# MCPGrundplatte8Eingabe_8Ausgabe.net
KiCad netlist of a schematic drawn in EAGLE
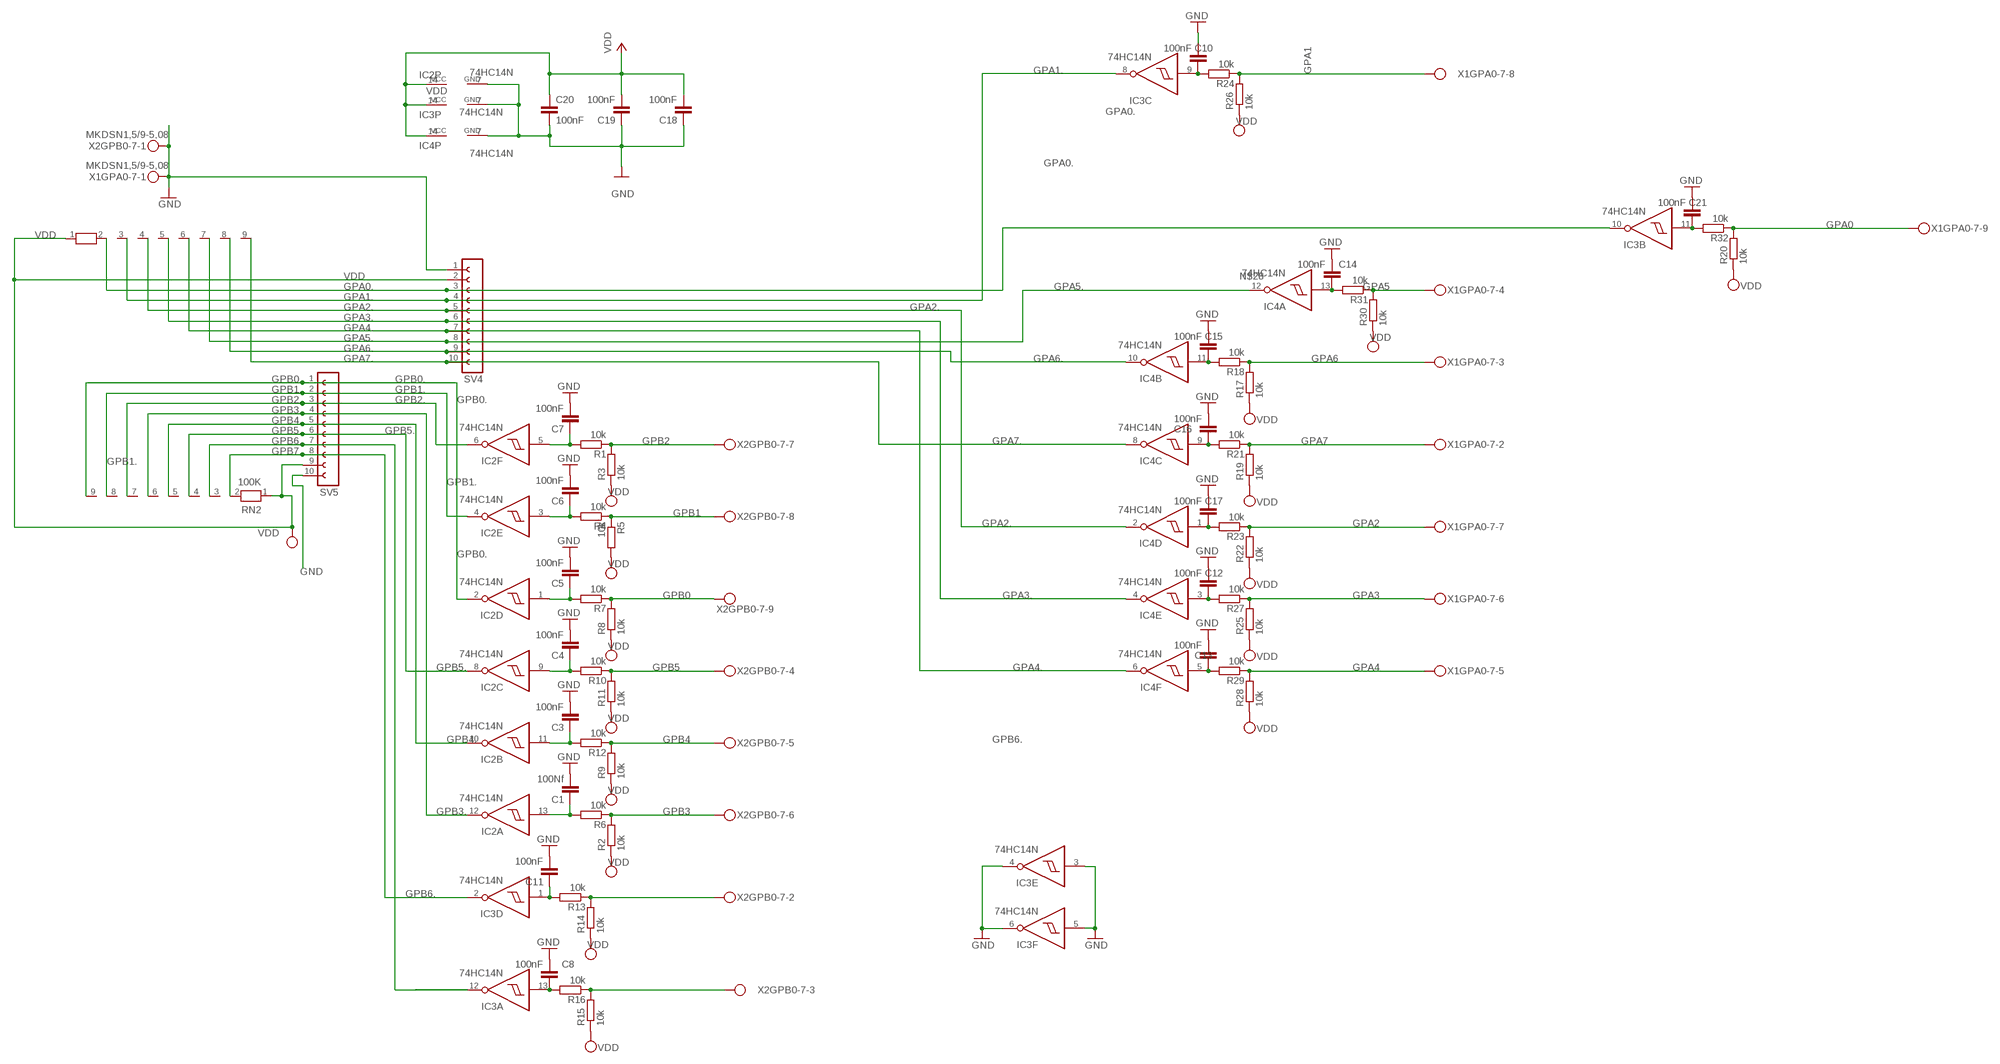
[diagram p0: schematic, sheet 1]

(export (version "E")
  (design (tool "Eeschema 10.0.6"))
  (components
    (comp (ref "C1")
      (value "100Nf")
      (footprint "eagle-import:C025-024X044")
      (libsource (lib "eagle-import") (part "C-EU025-024X044"))
    )
    (comp (ref "C3")
      (value "100nF")
      (footprint "eagle-import:C025-024X044")
      (libsource (lib "eagle-import") (part "C-EU025-024X044"))
    )
    (comp (ref "C4")
      (value "100nF")
      (footprint "eagle-import:C025-024X044")
      (libsource (lib "eagle-import") (part "C-EU025-024X044"))
    )
    (comp (ref "C5")
      (value "100nF")
      (footprint "eagle-import:C025-024X044")
      (libsource (lib "eagle-import") (part "C-EU025-024X044"))
    )
    (comp (ref "C6")
      (value "100nF")
      (footprint "eagle-import:C025-024X044")
      (libsource (lib "eagle-import") (part "C-EU025-024X044"))
    )
    (comp (ref "C7")
      (value "100nF")
      (footprint "eagle-import:C025-024X044")
      (libsource (lib "eagle-import") (part "C-EU025-024X044"))
    )
    (comp (ref "C8")
      (value "100nF")
      (footprint "eagle-import:C025-024X044")
      (libsource (lib "eagle-import") (part "C-EU025-024X044"))
    )
    (comp (ref "C10")
      (value "100nF")
      (footprint "eagle-import:C025-024X044")
      (libsource (lib "eagle-import") (part "C-EU025-024X044"))
    )
    (comp (ref "C11")
      (value "100nF")
      (footprint "eagle-import:C025-024X044")
      (libsource (lib "eagle-import") (part "C-EU025-024X044"))
    )
    (comp (ref "C12")
      (value "100nF")
      (footprint "eagle-import:C025-024X044")
      (libsource (lib "eagle-import") (part "C-EU025-024X044"))
    )
    (comp (ref "C13")
      (value "100nF")
      (footprint "eagle-import:C025-024X044")
      (libsource (lib "eagle-import") (part "C-EU025-024X044"))
    )
    (comp (ref "C14")
      (value "100nF")
      (footprint "eagle-import:C025-024X044")
      (libsource (lib "eagle-import") (part "C-EU025-024X044"))
    )
    (comp (ref "C15")
      (value "100nF")
      (footprint "eagle-import:C025-024X044")
      (libsource (lib "eagle-import") (part "C-EU025-024X044"))
    )
    (comp (ref "C16")
      (value "100nF")
      (footprint "eagle-import:C025-024X044")
      (libsource (lib "eagle-import") (part "C-EU025-024X044"))
    )
    (comp (ref "C17")
      (value "100nF")
      (footprint "eagle-import:C025-024X044")
      (libsource (lib "eagle-import") (part "C-EU025-024X044"))
    )
    (comp (ref "C18")
      (value "100nF")
      (footprint "eagle-import:C025-024X044")
      (libsource (lib "eagle-import") (part "C-EU025-024X044"))
    )
    (comp (ref "C19")
      (value "100nF")
      (footprint "eagle-import:C025-024X044")
      (libsource (lib "eagle-import") (part "C-EU025-024X044"))
    )
    (comp (ref "C20")
      (value "100nF")
      (footprint "eagle-import:C025-024X044")
      (libsource (lib "eagle-import") (part "C-EU025-024X044"))
    )
    (comp (ref "C21")
      (value "100nF")
      (footprint "eagle-import:C025-024X044")
      (libsource (lib "eagle-import") (part "C-EU025-024X044"))
    )
    (comp (ref "IC2")
      (value "74HC14N")
      (footprint "eagle-import:DIL14")
      (libsource (lib "eagle-import") (part "7414NHC"))
    )
    (comp (ref "IC3")
      (value "74HC14N")
      (footprint "eagle-import:DIL14")
      (libsource (lib "eagle-import") (part "7414NHC"))
    )
    (comp (ref "IC4")
      (value "74HC14N")
      (footprint "eagle-import:DIL14")
      (libsource (lib "eagle-import") (part "7414NHC"))
    )
    (comp (ref "R1")
      (value "10k")
      (footprint "eagle-import:0207_10")
      (libsource (lib "eagle-import") (part "R-EU_0207/10"))
    )
    (comp (ref "R2")
      (value "10k")
      (footprint "eagle-import:0207_10")
      (libsource (lib "eagle-import") (part "R-EU_0207/10"))
    )
    (comp (ref "R3")
      (value "10k")
      (footprint "eagle-import:0207_10")
      (libsource (lib "eagle-import") (part "R-EU_0207/10"))
    )
    (comp (ref "R4")
      (value "10k")
      (footprint "eagle-import:0207_10")
      (libsource (lib "eagle-import") (part "R-EU_0207/10"))
    )
    (comp (ref "R5")
      (value "10k")
      (footprint "eagle-import:0207_10")
      (libsource (lib "eagle-import") (part "R-EU_0207/10"))
    )
    (comp (ref "R6")
      (value "10k")
      (footprint "eagle-import:0207_10")
      (libsource (lib "eagle-import") (part "R-EU_0207/10"))
    )
    (comp (ref "R7")
      (value "10k")
      (footprint "eagle-import:0207_10")
      (libsource (lib "eagle-import") (part "R-EU_0207/10"))
    )
    (comp (ref "R8")
      (value "10k")
      (footprint "eagle-import:0207_10")
      (libsource (lib "eagle-import") (part "R-EU_0207/10"))
    )
    (comp (ref "R9")
      (value "10k")
      (footprint "eagle-import:0207_10")
      (libsource (lib "eagle-import") (part "R-EU_0207/10"))
    )
    (comp (ref "R10")
      (value "10k")
      (footprint "eagle-import:0207_10")
      (libsource (lib "eagle-import") (part "R-EU_0207/10"))
    )
    (comp (ref "R11")
      (value "10k")
      (footprint "eagle-import:0207_10")
      (libsource (lib "eagle-import") (part "R-EU_0207/10"))
    )
    (comp (ref "R12")
      (value "10k")
      (footprint "eagle-import:0207_10")
      (libsource (lib "eagle-import") (part "R-EU_0207/10"))
    )
    (comp (ref "R13")
      (value "10k")
      (footprint "eagle-import:0207_10")
      (libsource (lib "eagle-import") (part "R-EU_0207/10"))
    )
    (comp (ref "R14")
      (value "10k")
      (footprint "eagle-import:0207_10")
      (libsource (lib "eagle-import") (part "R-EU_0207/10"))
    )
    (comp (ref "R15")
      (value "10k")
      (footprint "eagle-import:0207_10")
      (libsource (lib "eagle-import") (part "R-EU_0207/10"))
    )
    (comp (ref "R16")
      (value "10k")
      (footprint "eagle-import:0207_10")
      (libsource (lib "eagle-import") (part "R-EU_0207/10"))
    )
    (comp (ref "R17")
      (value "10k")
      (footprint "eagle-import:0207_10")
      (libsource (lib "eagle-import") (part "R-EU_0207/10"))
    )
    (comp (ref "R18")
      (value "10k")
      (footprint "eagle-import:0207_10")
      (libsource (lib "eagle-import") (part "R-EU_0207/10"))
    )
    (comp (ref "R19")
      (value "10k")
      (footprint "eagle-import:0207_10")
      (libsource (lib "eagle-import") (part "R-EU_0207/10"))
    )
    (comp (ref "R20")
      (value "10k")
      (footprint "eagle-import:0207_10")
      (libsource (lib "eagle-import") (part "R-EU_0207/10"))
    )
    (comp (ref "R21")
      (value "10k")
      (footprint "eagle-import:0207_10")
      (libsource (lib "eagle-import") (part "R-EU_0207/10"))
    )
    (comp (ref "R22")
      (value "10k")
      (footprint "eagle-import:0207_10")
      (libsource (lib "eagle-import") (part "R-EU_0207/10"))
    )
    (comp (ref "R23")
      (value "10k")
      (footprint "eagle-import:0207_10")
      (libsource (lib "eagle-import") (part "R-EU_0207/10"))
    )
    (comp (ref "R24")
      (value "10k")
      (footprint "eagle-import:0207_10")
      (libsource (lib "eagle-import") (part "R-EU_0207/10"))
    )
    (comp (ref "R25")
      (value "10k")
      (footprint "eagle-import:0207_10")
      (libsource (lib "eagle-import") (part "R-EU_0207/10"))
    )
    (comp (ref "R26")
      (value "10k")
      (footprint "eagle-import:0207_10")
      (libsource (lib "eagle-import") (part "R-EU_0207/10"))
    )
    (comp (ref "R27")
      (value "10k")
      (footprint "eagle-import:0207_10")
      (libsource (lib "eagle-import") (part "R-EU_0207/10"))
    )
    (comp (ref "R28")
      (value "10k")
      (footprint "eagle-import:0207_10")
      (libsource (lib "eagle-import") (part "R-EU_0207/10"))
    )
    (comp (ref "R29")
      (value "10k")
      (footprint "eagle-import:0207_10")
      (libsource (lib "eagle-import") (part "R-EU_0207/10"))
    )
    (comp (ref "R30")
      (value "10k")
      (footprint "eagle-import:0207_10")
      (libsource (lib "eagle-import") (part "R-EU_0207/10"))
    )
    (comp (ref "R31")
      (value "10k")
      (footprint "eagle-import:0207_10")
      (libsource (lib "eagle-import") (part "R-EU_0207/10"))
    )
    (comp (ref "R32")
      (value "10k")
      (footprint "eagle-import:0207_10")
      (libsource (lib "eagle-import") (part "R-EU_0207/10"))
    )
    (comp (ref "RN1")
      (value "100K")
      (footprint "eagle-import:RN-9")
      (fields (field (name "SPICEPREFIX") "X"))
      (libsource (lib "eagle-import") (part "RN08"))
    )
    (comp (ref "RN2")
      (value "100K")
      (footprint "eagle-import:RN-9")
      (libsource (lib "eagle-import") (part "RN08"))
    )
    (comp (ref "SV4")
      (value "FE10-1")
      (footprint "eagle-import:FE10")
      (libsource (lib "eagle-import") (part "FE10-1"))
    )
    (comp (ref "SV5")
      (value "FE10-1")
      (footprint "eagle-import:FE10")
      (libsource (lib "eagle-import") (part "FE10-1"))
    )
    (comp (ref "X1GPA0-7")
      (value "MKDSN1,5/9-5,08")
      (footprint "eagle-import:MKDSN1,5_9-5,08")
      (libsource (lib "eagle-import") (part "MKDSN1,5/9-5,08"))
    )
    (comp (ref "X2GPB0-7")
      (value "MKDSN1,5/9-5,08")
      (footprint "eagle-import:MKDSN1,5_9-5,08")
      (libsource (lib "eagle-import") (part "MKDSN1,5/9-5,08"))
    )
  )
  (nets
    (net (code "1") (name "/GPA0") (class "Default")
      (node (ref "R20") (pin "2") (pinfunction "2_2") (pintype "passive"))
      (node (ref "R32") (pin "1") (pinfunction "1_1") (pintype "passive"))
      (node (ref "X1GPA0-7") (pin "9") (pinfunction "KL_9") (pintype "passive"))
    )
    (net (code "2") (name "/GPA0.") (class "Default")
      (node (ref "IC3") (pin "10") (pinfunction "O_10") (pintype "output"))
      (node (ref "RN1") (pin "2") (pinfunction "2_2") (pintype "passive"))
      (node (ref "SV4") (pin "3") (pinfunction "3_3") (pintype "passive"))
    )
    (net (code "3") (name "/GPA1") (class "Default")
      (node (ref "R24") (pin "1") (pinfunction "1_1") (pintype "passive"))
      (node (ref "R26") (pin "2") (pinfunction "2_2") (pintype "passive"))
      (node (ref "X1GPA0-7") (pin "8") (pinfunction "KL_8") (pintype "passive"))
    )
    (net (code "4") (name "/GPA1.") (class "Default")
      (node (ref "IC3") (pin "8") (pinfunction "O_8") (pintype "output"))
      (node (ref "RN1") (pin "3") (pinfunction "3_3") (pintype "passive"))
      (node (ref "SV4") (pin "4") (pinfunction "4_4") (pintype "passive"))
    )
    (net (code "5") (name "/GPA2") (class "Default")
      (node (ref "R22") (pin "2") (pinfunction "2_2") (pintype "passive"))
      (node (ref "R23") (pin "1") (pinfunction "1_1") (pintype "passive"))
      (node (ref "X1GPA0-7") (pin "7") (pinfunction "KL_7") (pintype "passive"))
    )
    (net (code "6") (name "/GPA2.") (class "Default")
      (node (ref "IC4") (pin "2") (pinfunction "O_2") (pintype "output"))
      (node (ref "RN1") (pin "4") (pinfunction "4_4") (pintype "passive"))
      (node (ref "SV4") (pin "5") (pinfunction "5_5") (pintype "passive"))
    )
    (net (code "7") (name "/GPA3") (class "Default")
      (node (ref "R25") (pin "2") (pinfunction "2_2") (pintype "passive"))
      (node (ref "R27") (pin "1") (pinfunction "1_1") (pintype "passive"))
      (node (ref "X1GPA0-7") (pin "6") (pinfunction "KL_6") (pintype "passive"))
    )
    (net (code "8") (name "/GPA3.") (class "Default")
      (node (ref "IC4") (pin "4") (pinfunction "O_4") (pintype "output"))
      (node (ref "RN1") (pin "5") (pinfunction "5_5") (pintype "passive"))
      (node (ref "SV4") (pin "6") (pinfunction "6_6") (pintype "passive"))
    )
    (net (code "9") (name "/GPA4") (class "Default")
      (node (ref "R28") (pin "2") (pinfunction "2_2") (pintype "passive"))
      (node (ref "R29") (pin "1") (pinfunction "1_1") (pintype "passive"))
      (node (ref "X1GPA0-7") (pin "5") (pinfunction "KL_5") (pintype "passive"))
    )
    (net (code "10") (name "/GPA4.") (class "Default")
      (node (ref "IC4") (pin "6") (pinfunction "O_6") (pintype "output"))
      (node (ref "RN1") (pin "6") (pinfunction "6_6") (pintype "passive"))
      (node (ref "SV4") (pin "7") (pinfunction "7_7") (pintype "passive"))
    )
    (net (code "11") (name "/GPA5") (class "Default")
      (node (ref "R30") (pin "2") (pinfunction "2_2") (pintype "passive"))
      (node (ref "R31") (pin "1") (pinfunction "1_1") (pintype "passive"))
      (node (ref "X1GPA0-7") (pin "4") (pinfunction "KL_4") (pintype "passive"))
    )
    (net (code "12") (name "/GPA5.") (class "Default")
      (node (ref "IC4") (pin "12") (pinfunction "O_12") (pintype "output"))
      (node (ref "RN1") (pin "7") (pinfunction "7_7") (pintype "passive"))
      (node (ref "SV4") (pin "8") (pinfunction "8_8") (pintype "passive"))
    )
    (net (code "13") (name "/GPA6") (class "Default")
      (node (ref "R17") (pin "2") (pinfunction "2_2") (pintype "passive"))
      (node (ref "R18") (pin "1") (pinfunction "1_1") (pintype "passive"))
      (node (ref "X1GPA0-7") (pin "3") (pinfunction "KL_3") (pintype "passive"))
    )
    (net (code "14") (name "/GPA6.") (class "Default")
      (node (ref "IC4") (pin "10") (pinfunction "O_10") (pintype "output"))
      (node (ref "RN1") (pin "8") (pinfunction "8_8") (pintype "passive"))
      (node (ref "SV4") (pin "9") (pinfunction "9_9") (pintype "passive"))
    )
    (net (code "15") (name "/GPA7") (class "Default")
      (node (ref "R19") (pin "2") (pinfunction "2_2") (pintype "passive"))
      (node (ref "R21") (pin "1") (pinfunction "1_1") (pintype "passive"))
      (node (ref "X1GPA0-7") (pin "2") (pinfunction "KL_2") (pintype "passive"))
    )
    (net (code "16") (name "/GPA7.") (class "Default")
      (node (ref "IC4") (pin "8") (pinfunction "O_8") (pintype "output"))
      (node (ref "RN1") (pin "9") (pinfunction "9_9") (pintype "passive"))
      (node (ref "SV4") (pin "10") (pinfunction "10_10") (pintype "passive"))
    )
    (net (code "17") (name "/GPB0") (class "Default")
      (node (ref "R7") (pin "1") (pinfunction "1_1") (pintype "passive"))
      (node (ref "R8") (pin "2") (pinfunction "2_2") (pintype "passive"))
      (node (ref "X2GPB0-7") (pin "9") (pinfunction "KL_9") (pintype "passive"))
    )
    (net (code "18") (name "/GPB0.") (class "Default")
      (node (ref "IC2") (pin "2") (pinfunction "O_2") (pintype "output"))
      (node (ref "RN2") (pin "9") (pinfunction "9_9") (pintype "passive"))
      (node (ref "SV5") (pin "1") (pinfunction "1_1") (pintype "passive"))
    )
    (net (code "19") (name "/GPB1") (class "Default")
      (node (ref "R4") (pin "1") (pinfunction "1_1") (pintype "passive"))
      (node (ref "R5") (pin "1") (pinfunction "1_1") (pintype "passive"))
      (node (ref "X2GPB0-7") (pin "8") (pinfunction "KL_8") (pintype "passive"))
    )
    (net (code "20") (name "/GPB1.") (class "Default")
      (node (ref "IC2") (pin "4") (pinfunction "O_4") (pintype "output"))
      (node (ref "RN2") (pin "8") (pinfunction "8_8") (pintype "passive"))
      (node (ref "SV5") (pin "2") (pinfunction "2_2") (pintype "passive"))
    )
    (net (code "21") (name "/GPB2") (class "Default")
      (node (ref "R1") (pin "1") (pinfunction "1_1") (pintype "passive"))
      (node (ref "R3") (pin "2") (pinfunction "2_2") (pintype "passive"))
      (node (ref "X2GPB0-7") (pin "7") (pinfunction "KL_7") (pintype "passive"))
    )
    (net (code "22") (name "/GPB2.") (class "Default")
      (node (ref "IC2") (pin "6") (pinfunction "O_6") (pintype "output"))
      (node (ref "RN2") (pin "7") (pinfunction "7_7") (pintype "passive"))
      (node (ref "SV5") (pin "3") (pinfunction "3_3") (pintype "passive"))
    )
    (net (code "23") (name "/GPB3") (class "Default")
      (node (ref "R2") (pin "2") (pinfunction "2_2") (pintype "passive"))
      (node (ref "R6") (pin "1") (pinfunction "1_1") (pintype "passive"))
      (node (ref "X2GPB0-7") (pin "6") (pinfunction "KL_6") (pintype "passive"))
    )
    (net (code "24") (name "/GPB3.") (class "Default")
      (node (ref "IC2") (pin "12") (pinfunction "O_12") (pintype "output"))
      (node (ref "RN2") (pin "6") (pinfunction "6_6") (pintype "passive"))
      (node (ref "SV5") (pin "4") (pinfunction "4_4") (pintype "passive"))
    )
    (net (code "25") (name "/GPB4") (class "Default")
      (node (ref "R12") (pin "1") (pinfunction "1_1") (pintype "passive"))
      (node (ref "R9") (pin "2") (pinfunction "2_2") (pintype "passive"))
      (node (ref "X2GPB0-7") (pin "5") (pinfunction "KL_5") (pintype "passive"))
    )
    (net (code "26") (name "/GPB4.") (class "Default")
      (node (ref "IC2") (pin "10") (pinfunction "O_10") (pintype "output"))
      (node (ref "RN2") (pin "5") (pinfunction "5_5") (pintype "passive"))
      (node (ref "SV5") (pin "5") (pinfunction "5_5") (pintype "passive"))
    )
    (net (code "27") (name "/GPB5") (class "Default")
      (node (ref "R10") (pin "1") (pinfunction "1_1") (pintype "passive"))
      (node (ref "R11") (pin "2") (pinfunction "2_2") (pintype "passive"))
      (node (ref "X2GPB0-7") (pin "4") (pinfunction "KL_4") (pintype "passive"))
    )
    (net (code "28") (name "/GPB5.") (class "Default")
      (node (ref "IC2") (pin "8") (pinfunction "O_8") (pintype "output"))
      (node (ref "RN2") (pin "4") (pinfunction "4_4") (pintype "passive"))
      (node (ref "SV5") (pin "6") (pinfunction "6_6") (pintype "passive"))
    )
    (net (code "29") (name "/GPB6.") (class "Default")
      (node (ref "IC3") (pin "12") (pinfunction "O_12") (pintype "output"))
      (node (ref "RN2") (pin "3") (pinfunction "3_3") (pintype "passive"))
      (node (ref "SV5") (pin "7") (pinfunction "7_7") (pintype "passive"))
    )
    (net (code "30") (name "/GPB7.") (class "Default")
      (node (ref "IC3") (pin "2") (pinfunction "O_2") (pintype "output"))
      (node (ref "RN2") (pin "2") (pinfunction "2_2") (pintype "passive"))
      (node (ref "SV5") (pin "8") (pinfunction "8_8") (pintype "passive"))
    )
    (net (code "32") (name "GND") (class "Default")
      (node (ref "C1") (pin "2") (pinfunction "2_2") (pintype "passive"))
      (node (ref "C10") (pin "2") (pinfunction "2_2") (pintype "passive"))
      (node (ref "C11") (pin "2") (pinfunction "2_2") (pintype "passive"))
      (node (ref "C12") (pin "2") (pinfunction "2_2") (pintype "passive"))
      (node (ref "C13") (pin "2") (pinfunction "2_2") (pintype "passive"))
      (node (ref "C14") (pin "2") (pinfunction "2_2") (pintype "passive"))
      (node (ref "C15") (pin "2") (pinfunction "2_2") (pintype "passive"))
      (node (ref "C16") (pin "2") (pinfunction "2_2") (pintype "passive"))
      (node (ref "C17") (pin "2") (pinfunction "2_2") (pintype "passive"))
      (node (ref "C18") (pin "1") (pinfunction "1_1") (pintype "passive"))
      (node (ref "C19") (pin "1") (pinfunction "1_1") (pintype "passive"))
      (node (ref "C20") (pin "2") (pinfunction "2_2") (pintype "passive"))
      (node (ref "C21") (pin "2") (pinfunction "2_2") (pintype "passive"))
      (node (ref "C3") (pin "2") (pinfunction "2_2") (pintype "passive"))
      (node (ref "C4") (pin "2") (pinfunction "2_2") (pintype "passive"))
      (node (ref "C5") (pin "2") (pinfunction "2_2") (pintype "passive"))
      (node (ref "C6") (pin "2") (pinfunction "2_2") (pintype "passive"))
      (node (ref "C7") (pin "2") (pinfunction "2_2") (pintype "passive"))
      (node (ref "C8") (pin "2") (pinfunction "2_2") (pintype "passive"))
      (node (ref "IC2") (pin "7") (pinfunction "GND_7") (pintype "power_in"))
      (node (ref "IC3") (pin "3") (pinfunction "I_3") (pintype "input"))
      (node (ref "IC3") (pin "4") (pinfunction "O_4") (pintype "output"))
      (node (ref "IC3") (pin "5") (pinfunction "I_5") (pintype "input"))
      (node (ref "IC3") (pin "6") (pinfunction "O_6") (pintype "output"))
      (node (ref "IC3") (pin "7") (pinfunction "GND_7") (pintype "power_in"))
      (node (ref "IC4") (pin "7") (pinfunction "GND_7") (pintype "power_in"))
      (node (ref "SV4") (pin "1") (pinfunction "1_1") (pintype "passive"))
      (node (ref "SV5") (pin "10") (pinfunction "10_10") (pintype "passive"))
      (node (ref "X1GPA0-7") (pin "1") (pinfunction "KL_1") (pintype "passive"))
      (node (ref "X2GPB0-7") (pin "1") (pinfunction "KL_1") (pintype "passive"))
    )
    (net (code "33") (name "Net-(IC2A-I)") (class "Default")
      (node (ref "C1") (pin "1") (pinfunction "1_1") (pintype "passive"))
      (node (ref "IC2") (pin "13") (pinfunction "I_13") (pintype "input"))
      (node (ref "R6") (pin "2") (pinfunction "2_2") (pintype "passive"))
    )
    (net (code "34") (name "Net-(IC2B-I)") (class "Default")
      (node (ref "C3") (pin "1") (pinfunction "1_1") (pintype "passive"))
      (node (ref "IC2") (pin "11") (pinfunction "I_11") (pintype "input"))
      (node (ref "R12") (pin "2") (pinfunction "2_2") (pintype "passive"))
    )
    (net (code "35") (name "Net-(IC2C-I)") (class "Default")
      (node (ref "C4") (pin "1") (pinfunction "1_1") (pintype "passive"))
      (node (ref "IC2") (pin "9") (pinfunction "I_9") (pintype "input"))
      (node (ref "R10") (pin "2") (pinfunction "2_2") (pintype "passive"))
    )
    (net (code "36") (name "Net-(IC2D-I)") (class "Default")
      (node (ref "C5") (pin "1") (pinfunction "1_1") (pintype "passive"))
      (node (ref "IC2") (pin "1") (pinfunction "I_1") (pintype "input"))
      (node (ref "R7") (pin "2") (pinfunction "2_2") (pintype "passive"))
    )
    (net (code "37") (name "Net-(IC2E-I)") (class "Default")
      (node (ref "C6") (pin "1") (pinfunction "1_1") (pintype "passive"))
      (node (ref "IC2") (pin "3") (pinfunction "I_3") (pintype "input"))
      (node (ref "R4") (pin "2") (pinfunction "2_2") (pintype "passive"))
    )
    (net (code "38") (name "Net-(IC2F-I)") (class "Default")
      (node (ref "C7") (pin "1") (pinfunction "1_1") (pintype "passive"))
      (node (ref "IC2") (pin "5") (pinfunction "I_5") (pintype "input"))
      (node (ref "R1") (pin "2") (pinfunction "2_2") (pintype "passive"))
    )
    (net (code "39") (name "Net-(IC3A-I)") (class "Default")
      (node (ref "C8") (pin "1") (pinfunction "1_1") (pintype "passive"))
      (node (ref "IC3") (pin "13") (pinfunction "I_13") (pintype "input"))
      (node (ref "R16") (pin "2") (pinfunction "2_2") (pintype "passive"))
    )
    (net (code "40") (name "Net-(IC3B-I)") (class "Default")
      (node (ref "C21") (pin "1") (pinfunction "1_1") (pintype "passive"))
      (node (ref "IC3") (pin "11") (pinfunction "I_11") (pintype "input"))
      (node (ref "R32") (pin "2") (pinfunction "2_2") (pintype "passive"))
    )
    (net (code "41") (name "Net-(IC3C-I)") (class "Default")
      (node (ref "C10") (pin "1") (pinfunction "1_1") (pintype "passive"))
      (node (ref "IC3") (pin "9") (pinfunction "I_9") (pintype "input"))
      (node (ref "R24") (pin "2") (pinfunction "2_2") (pintype "passive"))
    )
    (net (code "42") (name "Net-(IC3D-I)") (class "Default")
      (node (ref "C11") (pin "1") (pinfunction "1_1") (pintype "passive"))
      (node (ref "IC3") (pin "1") (pinfunction "I_1") (pintype "input"))
      (node (ref "R13") (pin "2") (pinfunction "2_2") (pintype "passive"))
    )
    (net (code "43") (name "Net-(IC4A-I)") (class "Default")
      (node (ref "C14") (pin "1") (pinfunction "1_1") (pintype "passive"))
      (node (ref "IC4") (pin "13") (pinfunction "I_13") (pintype "input"))
      (node (ref "R31") (pin "2") (pinfunction "2_2") (pintype "passive"))
    )
    (net (code "44") (name "Net-(IC4B-I)") (class "Default")
      (node (ref "C15") (pin "1") (pinfunction "1_1") (pintype "passive"))
      (node (ref "IC4") (pin "11") (pinfunction "I_11") (pintype "input"))
      (node (ref "R18") (pin "2") (pinfunction "2_2") (pintype "passive"))
    )
    (net (code "45") (name "Net-(IC4C-I)") (class "Default")
      (node (ref "C16") (pin "1") (pinfunction "1_1") (pintype "passive"))
      (node (ref "IC4") (pin "9") (pinfunction "I_9") (pintype "input"))
      (node (ref "R21") (pin "2") (pinfunction "2_2") (pintype "passive"))
    )
    (net (code "46") (name "Net-(IC4D-I)") (class "Default")
      (node (ref "C17") (pin "1") (pinfunction "1_1") (pintype "passive"))
      (node (ref "IC4") (pin "1") (pinfunction "I_1") (pintype "input"))
      (node (ref "R23") (pin "2") (pinfunction "2_2") (pintype "passive"))
    )
    (net (code "47") (name "Net-(IC4E-I)") (class "Default")
      (node (ref "C12") (pin "1") (pinfunction "1_1") (pintype "passive"))
      (node (ref "IC4") (pin "3") (pinfunction "I_3") (pintype "input"))
      (node (ref "R27") (pin "2") (pinfunction "2_2") (pintype "passive"))
    )
    (net (code "48") (name "Net-(IC4F-I)") (class "Default")
      (node (ref "C13") (pin "1") (pinfunction "1_1") (pintype "passive"))
      (node (ref "IC4") (pin "5") (pinfunction "I_5") (pintype "input"))
      (node (ref "R29") (pin "2") (pinfunction "2_2") (pintype "passive"))
    )
    (net (code "49") (name "Net-(X2GPB0-7B-KL)") (class "Default")
      (node (ref "R13") (pin "1") (pinfunction "1_1") (pintype "passive"))
      (node (ref "R14") (pin "2") (pinfunction "2_2") (pintype "passive"))
      (node (ref "X2GPB0-7") (pin "2") (pinfunction "KL_2") (pintype "passive"))
    )
    (net (code "50") (name "Net-(X2GPB0-7C-KL)") (class "Default")
      (node (ref "R15") (pin "2") (pinfunction "2_2") (pintype "passive"))
      (node (ref "R16") (pin "1") (pinfunction "1_1") (pintype "passive"))
      (node (ref "X2GPB0-7") (pin "3") (pinfunction "KL_3") (pintype "passive"))
    )
    (net (code "51") (name "VDD") (class "Default")
      (node (ref "C18") (pin "2") (pinfunction "2_2") (pintype "passive"))
      (node (ref "C19") (pin "2") (pinfunction "2_2") (pintype "passive"))
      (node (ref "C20") (pin "1") (pinfunction "1_1") (pintype "passive"))
      (node (ref "IC2") (pin "14") (pinfunction "VCC_14") (pintype "power_in"))
      (node (ref "IC3") (pin "14") (pinfunction "VCC_14") (pintype "power_in"))
      (node (ref "IC4") (pin "14") (pinfunction "VCC_14") (pintype "power_in"))
      (node (ref "R11") (pin "1") (pinfunction "1_1") (pintype "passive"))
      (node (ref "R14") (pin "1") (pinfunction "1_1") (pintype "passive"))
      (node (ref "R15") (pin "1") (pinfunction "1_1") (pintype "passive"))
      (node (ref "R17") (pin "1") (pinfunction "1_1") (pintype "passive"))
      (node (ref "R19") (pin "1") (pinfunction "1_1") (pintype "passive"))
      (node (ref "R2") (pin "1") (pinfunction "1_1") (pintype "passive"))
      (node (ref "R20") (pin "1") (pinfunction "1_1") (pintype "passive"))
      (node (ref "R22") (pin "1") (pinfunction "1_1") (pintype "passive"))
      (node (ref "R25") (pin "1") (pinfunction "1_1") (pintype "passive"))
      (node (ref "R26") (pin "1") (pinfunction "1_1") (pintype "passive"))
      (node (ref "R28") (pin "1") (pinfunction "1_1") (pintype "passive"))
      (node (ref "R3") (pin "1") (pinfunction "1_1") (pintype "passive"))
      (node (ref "R30") (pin "1") (pinfunction "1_1") (pintype "passive"))
      (node (ref "R5") (pin "2") (pinfunction "2_2") (pintype "passive"))
      (node (ref "R8") (pin "1") (pinfunction "1_1") (pintype "passive"))
      (node (ref "R9") (pin "1") (pinfunction "1_1") (pintype "passive"))
      (node (ref "RN1") (pin "1") (pinfunction "1_1") (pintype "passive"))
      (node (ref "RN2") (pin "1") (pinfunction "1_1") (pintype "passive"))
      (node (ref "SV4") (pin "2") (pinfunction "2_2") (pintype "passive"))
      (node (ref "SV5") (pin "9") (pinfunction "9_9") (pintype "passive"))
    )
  )
)
